# Schematic.net
KiCad netlist of a schematic drawn in Altium Designer
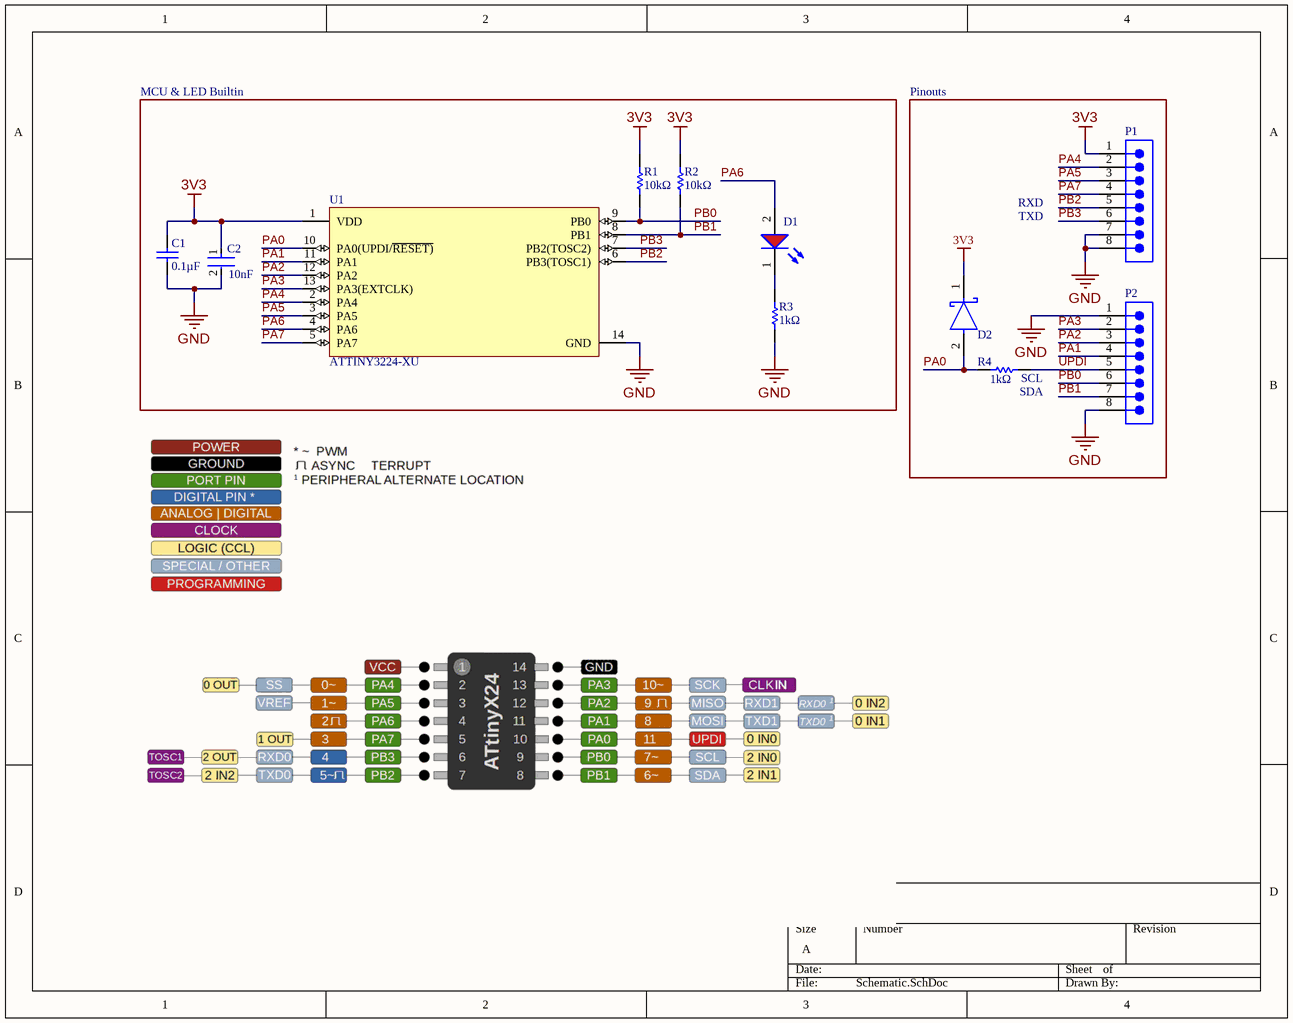
[diagram p0: Schematic.SchDoc]

(export (version "E")
  (design (tool "Eeschema 10.0.6"))
  (components
    (comp (ref "C1")
      (value "0.1µF")
      (footprint "CAPC3216X100X50LL20T25")
      (description "Chip Capacitor, 100 nF, +/- 10%, 25 V, -55 to 125 degC, 1206 (3216 Metric), RoHS, Tape and Reel")
      (fields (field (name "MANUFACTURER") "Kemet"))
      (libsource (lib "Altium Content Vault") (part "CAP-NP-2"))
    )
    (comp (ref "C2")
      (value "10nF")
      (footprint "FP-C1206C-EB-MFG")
      (description "CAP CER 10000PF 100V X7R 1206")
      (fields
        (field (name "OCTOPART") "https://octopart.com/c1206c103j1ractu-kemet-121270")
        (field (name "MANUFACTURER") "KEMET")
      )
      (libsource (lib "Altium Content Vault") (part "b4654b650e69147ec39a6b967a45e02"))
    )
    (comp (ref "D1")
      (value "150120RS75000")
      (footprint "WL-SMCW_1206_150120xx75000")
      (description "WL-SMCW SMT Mono-Color Chip LED Waterclear")
      (libsource (lib "Altium Content Vault") (part "LED_Red_2A-1K"))
    )
    (comp (ref "D2")
      (value "SS14-E3/61T")
      (footprint "FP-95400-MFG")
      (description "DIODE SCHOTTKY 40V 1A DO214AC")
      (fields
        (field (name "OCTOPART") "https://octopart.com/ss14-e3%2F61t-vishay-39552847")
        (field (name "MANUFACTURER") "Vishay")
      )
      (libsource (lib "Altium Content Vault") (part "1d6ec82d83fb6aee721767c19dac4b9"))
    )
    (comp (ref "P1")
      (value "61300811121")
      (footprint "61300811121")
      (libsource (lib "Altium Content Vault") (part "Header_Male_1R_08P"))
    )
    (comp (ref "P2")
      (value "61300811121")
      (footprint "61300811121")
      (libsource (lib "Altium Content Vault") (part "Header_Male_1R_08P"))
    )
    (comp (ref "R1")
      (value "10kΩ")
      (footprint "RESC3116X65X40LL10T20")
      (description "Chip Resistor, 10 KOhm, +/- 1%, 0.25 W, -55 to 155 degC, 1206 (3216 Metric), RoHS, Tape and Reel")
      (fields (field (name "TOLERANCE") "1%") (field (name "MANUFACTURER") "Yageo"))
      (libsource (lib "Altium Content Vault") (part "RES-2"))
    )
    (comp (ref "R2")
      (value "10kΩ")
      (footprint "RESC3116X65X40LL10T20")
      (description "Chip Resistor, 10 KOhm, +/- 1%, 0.25 W, -55 to 155 degC, 1206 (3216 Metric), RoHS, Tape and Reel")
      (fields (field (name "TOLERANCE") "1%") (field (name "MANUFACTURER") "Yageo"))
      (libsource (lib "Altium Content Vault") (part "RES-2"))
    )
    (comp (ref "R3")
      (value "1kΩ")
      (footprint "RESC3116X65X40LL10T20")
      (description "Chip Resistor, 1 KOhm, +/- 1%, 0.25 W, -55 to 155 degC, 1206 (3216 Metric), RoHS, Tape and Reel")
      (fields (field (name "TOLERANCE") "1%") (field (name "MANUFACTURER") "Yageo"))
      (libsource (lib "Altium Content Vault") (part "RES-2"))
    )
    (comp (ref "R4")
      (value "1kΩ")
      (footprint "RESC3116X65X40LL10T20")
      (description "Chip Resistor, 1 KOhm, +/- 1%, 0.25 W, -55 to 155 degC, 1206 (3216 Metric), RoHS, Tape and Reel")
      (fields (field (name "TOLERANCE") "1%") (field (name "MANUFACTURER") "Yageo"))
      (libsource (lib "Altium Content Vault") (part "RES-2"))
    )
    (comp (ref "U1")
      (value "ATTINY3224-XU")
      (footprint "FP-C04-087-ST-MFG")
      (description "ATTINY3224-XU Microcontroller 8-Bit AVR RISC 32KB Flash 1.8V to 5.5V 14-Pin TSSOP Tube")
      (libsource (lib "Altium Content Vault") (part "af96ba96504569538fca35b5c374a83"))
    )
  )
  (nets
    (net (code "1") (name "/PA0") (class "Default")
      (node (ref "D2") (pin "2") (pinfunction "A_2") (pintype "passive"))
      (node (ref "R4") (pin "1") (pinfunction "1_1") (pintype "passive"))
      (node (ref "U1") (pin "10") (pinfunction "PA0(UPDI/~{RESET)}_10") (pintype "bidirectional"))
    )
    (net (code "2") (name "/PA1") (class "Default")
      (node (ref "P2") (pin "4") (pinfunction "4_4") (pintype "passive"))
      (node (ref "U1") (pin "11") (pinfunction "PA1_11") (pintype "bidirectional"))
    )
    (net (code "3") (name "/PA2") (class "Default")
      (node (ref "P2") (pin "3") (pinfunction "3_3") (pintype "passive"))
      (node (ref "U1") (pin "12") (pinfunction "PA2_12") (pintype "bidirectional"))
    )
    (net (code "4") (name "/PA3") (class "Default")
      (node (ref "P2") (pin "2") (pinfunction "2_2") (pintype "passive"))
      (node (ref "U1") (pin "13") (pinfunction "PA3(EXTCLK)_13") (pintype "bidirectional"))
    )
    (net (code "5") (name "/PA4") (class "Default")
      (node (ref "P1") (pin "2") (pinfunction "2_2") (pintype "passive"))
      (node (ref "U1") (pin "2") (pinfunction "PA4_2") (pintype "bidirectional"))
    )
    (net (code "6") (name "/PA5") (class "Default")
      (node (ref "P1") (pin "3") (pinfunction "3_3") (pintype "passive"))
      (node (ref "U1") (pin "3") (pinfunction "PA5_3") (pintype "bidirectional"))
    )
    (net (code "7") (name "/PA6") (class "Default")
      (node (ref "D1") (pin "2") (pinfunction "A_2") (pintype "passive"))
      (node (ref "U1") (pin "4") (pinfunction "PA6_4") (pintype "bidirectional"))
    )
    (net (code "8") (name "/PA7") (class "Default")
      (node (ref "P1") (pin "4") (pinfunction "4_4") (pintype "passive"))
      (node (ref "U1") (pin "5") (pinfunction "PA7_5") (pintype "bidirectional"))
    )
    (net (code "9") (name "/PB0") (class "Default")
      (node (ref "P2") (pin "6") (pinfunction "6_6") (pintype "passive"))
      (node (ref "R1") (pin "1") (pinfunction "1_1") (pintype "passive"))
      (node (ref "U1") (pin "9") (pinfunction "PB0_9") (pintype "bidirectional"))
    )
    (net (code "10") (name "/PB1") (class "Default")
      (node (ref "P2") (pin "7") (pinfunction "7_7") (pintype "passive"))
      (node (ref "R2") (pin "1") (pinfunction "1_1") (pintype "passive"))
      (node (ref "U1") (pin "8") (pinfunction "PB1_8") (pintype "bidirectional"))
    )
    (net (code "11") (name "/PB2") (class "Default")
      (node (ref "P1") (pin "5") (pinfunction "5_5") (pintype "passive"))
      (node (ref "U1") (pin "6") (pinfunction "PB3(TOSC1)_6") (pintype "bidirectional"))
    )
    (net (code "12") (name "/PB3") (class "Default")
      (node (ref "P1") (pin "6") (pinfunction "6_6") (pintype "passive"))
      (node (ref "U1") (pin "7") (pinfunction "PB2(TOSC2)_7") (pintype "bidirectional"))
    )
    (net (code "13") (name "/UPDI") (class "Default")
      (node (ref "P2") (pin "5") (pinfunction "5_5") (pintype "passive"))
      (node (ref "R4") (pin "2") (pinfunction "2_2") (pintype "passive"))
    )
    (net (code "14") (name "3V3") (class "Default")
      (node (ref "C1") (pin "2") (pinfunction "2_2") (pintype "passive"))
      (node (ref "C2") (pin "1") (pinfunction "1_1") (pintype "passive"))
      (node (ref "D2") (pin "1") (pinfunction "C_1") (pintype "passive"))
      (node (ref "P1") (pin "1") (pinfunction "1_1") (pintype "passive"))
      (node (ref "R1") (pin "2") (pinfunction "2_2") (pintype "passive"))
      (node (ref "R2") (pin "2") (pinfunction "2_2") (pintype "passive"))
      (node (ref "U1") (pin "1") (pinfunction "VDD_1") (pintype "power_in"))
    )
    (net (code "15") (name "GND") (class "Default")
      (node (ref "C1") (pin "1") (pinfunction "1_1") (pintype "passive"))
      (node (ref "C2") (pin "2") (pinfunction "2_2") (pintype "passive"))
      (node (ref "P1") (pin "7") (pinfunction "7_7") (pintype "passive"))
      (node (ref "P1") (pin "8") (pinfunction "8_8") (pintype "passive"))
      (node (ref "P2") (pin "1") (pinfunction "1_1") (pintype "passive"))
      (node (ref "P2") (pin "8") (pinfunction "8_8") (pintype "passive"))
      (node (ref "R3") (pin "1") (pinfunction "1_1") (pintype "passive"))
      (node (ref "U1") (pin "14") (pinfunction "GND_14") (pintype "power_in"))
    )
    (net (code "16") (name "Net-(D1-K)") (class "Default")
      (node (ref "D1") (pin "1") (pinfunction "K_1") (pintype "passive"))
      (node (ref "R3") (pin "2") (pinfunction "2_2") (pintype "passive"))
    )
  )
)
